# sat-smd.net
KiCad netlist of a schematic drawn in Altium Designer
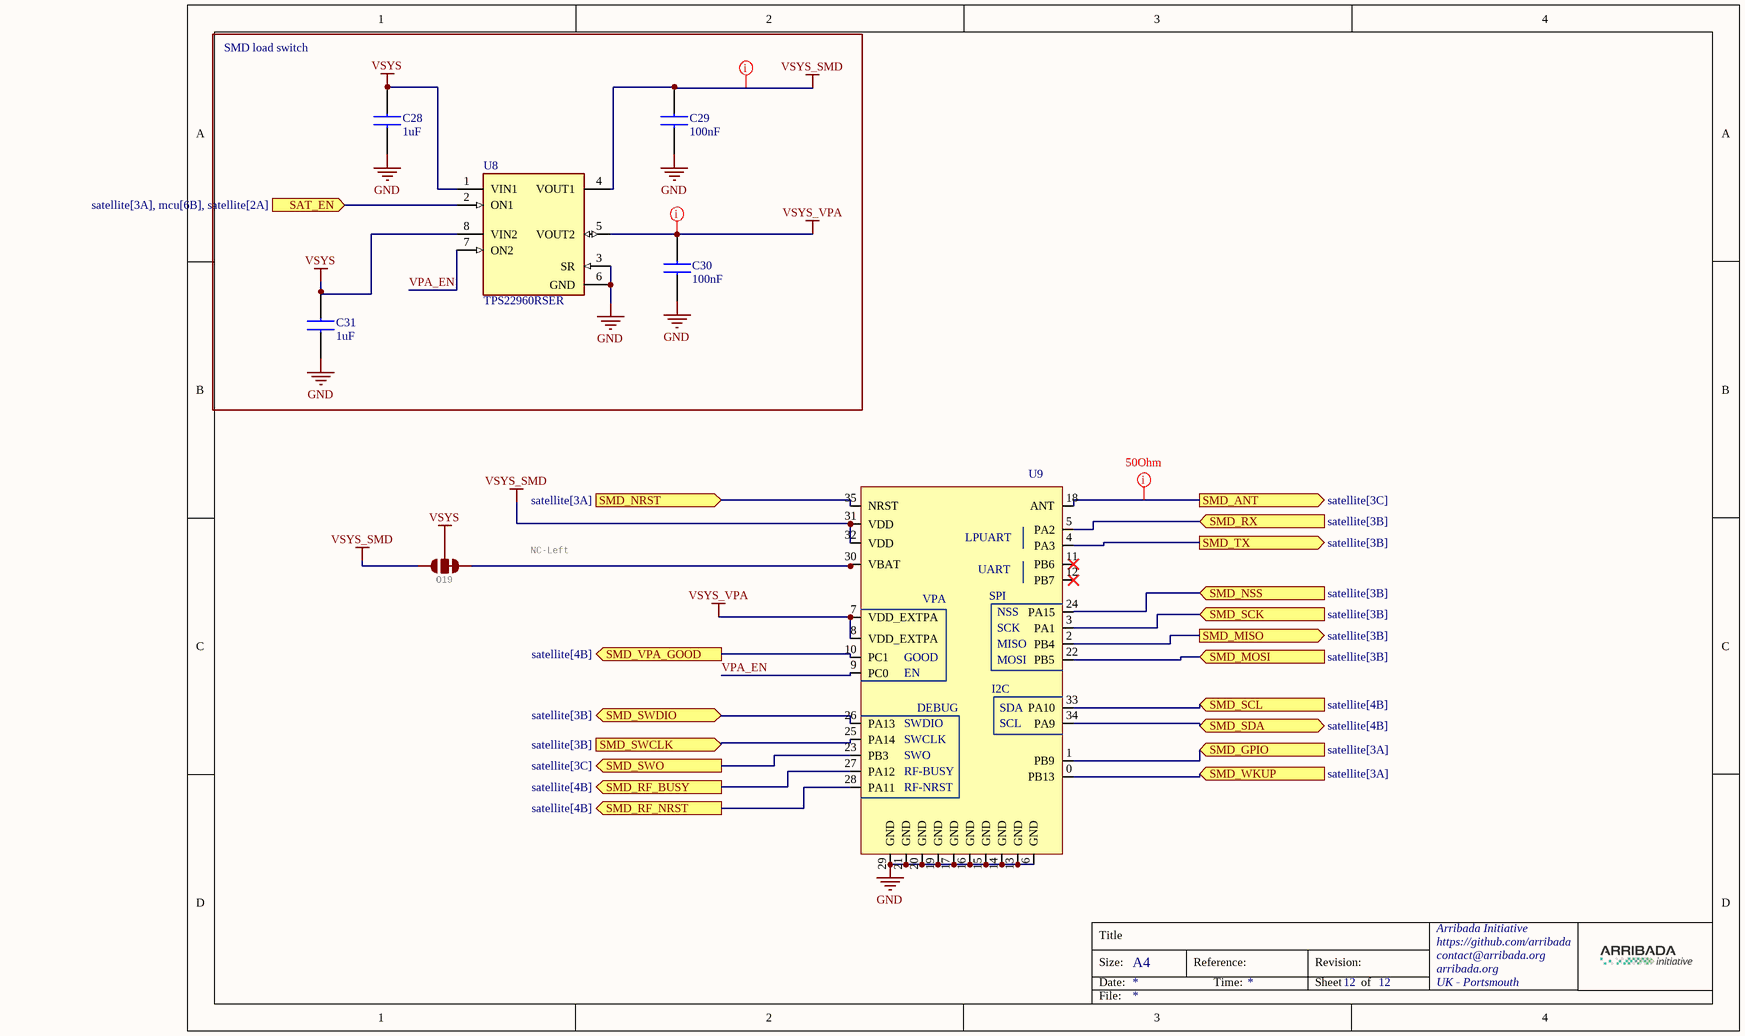
[diagram p0: sat-smd.SchDoc]

(export (version "E")
  (design (tool "Eeschema 10.0.6"))
  (components
    (comp (ref "C28")
      (value "1uF")
      (footprint "CAPC1005X55N")
      (description "Multilayer Ceramic Capacitors MLCC - SMD/SMT 1.0UF 10V 10% 0402")
      (fields
        (field (name "MANUFACTURER_PART_NUMBER") "GRM155Z71A105KE01J")
        (field (name "MOUSER PART NUMBER") "81-GRM155Z71A105KE1J")
      )
      (libsource (lib "stm32wl-dev") (part "GRM155Z71A105KE01J"))
    )
    (comp (ref "C29")
      (value "100nF")
      (footprint "0402")
      (description "Multilayer Ceramic Capacitors MLCC - SMD/SMT 0.1 uF 16 VDC 10% 0402 X7R")
      (fields
        (field (name "MANUFACTURER_PART_NUMBER") "CC0402KRX7R7BB104")
        (field (name "MANUFACTURER") "YAGEO")
      )
      (libsource (lib "stm32wl-dev") (part "GRM155R71C104KA88D"))
    )
    (comp (ref "C30")
      (value "100nF")
      (footprint "0402")
      (description "Multilayer Ceramic Capacitors MLCC - SMD/SMT 0.1 uF 16 VDC 10% 0402 X7R")
      (fields
        (field (name "MANUFACTURER_PART_NUMBER") "CC0402KRX7R7BB104")
        (field (name "MANUFACTURER") "YAGEO")
      )
      (libsource (lib "stm32wl-dev") (part "GRM155R71C104KA88D"))
    )
    (comp (ref "C31")
      (value "1uF")
      (footprint "CAPC1005X55N")
      (description "Multilayer Ceramic Capacitors MLCC - SMD/SMT 1.0UF 10V 10% 0402")
      (fields
        (field (name "MANUFACTURER_PART_NUMBER") "GRM155Z71A105KE01J")
        (field (name "MOUSER PART NUMBER") "81-GRM155Z71A105KE1J")
      )
      (libsource (lib "stm32wl-dev") (part "GRM155Z71A105KE01J"))
    )
    (comp (ref "O19")
      (value "NC-Left")
      (footprint "SMT-JUMPER_3_2-NCLEFT_TRACE_SILK")
      (libsource (lib "stm32wl-dev") (part "JUMPER-SMT_3_2-NCLEFT_TRACE_SILK"))
    )
    (comp (ref "U8")
      (value "TPS22960RSER")
      (footprint "stm32wl-dev:TPS22960RSER")
      (description "Power Switch ICs - Power Distribution Low Input VTG Dual L oad Switch")
      (fields (field (name "MOUSER PART NUMBER") "595-TPS22960RSER"))
      (libsource (lib "stm32wl-dev") (part "TPS22960RSER"))
    )
    (comp (ref "U9")
      (value "stm32wl-SMD")
      (footprint "stm32wl-SMD_noLegs")
      (description "Arribada SMD module Argos comunication with PA GR5504")
      (libsource (lib "stm32wl-dev") (part "stm32wl-SMD"))
    )
  )
  (nets
    (net (code "1") (name "/SAT_EN") (class "Default")
      (node (ref "U8") (pin "2") (pinfunction "ON1_2") (pintype "input"))
    )
    (net (code "2") (name "/SMD_ANT") (class "Default")
      (node (ref "U9") (pin "18") (pinfunction "ANT_18") (pintype "passive"))
    )
    (net (code "3") (name "/SMD_GPIO") (class "Default")
      (node (ref "U9") (pin "1") (pinfunction "PB9_1") (pintype "passive"))
    )
    (net (code "4") (name "/SMD_MISO") (class "Default")
      (node (ref "U9") (pin "2") (pinfunction "PB4_2") (pintype "passive"))
    )
    (net (code "5") (name "/SMD_MOSI") (class "Default")
      (node (ref "U9") (pin "22") (pinfunction "PB5_22") (pintype "passive"))
    )
    (net (code "6") (name "/SMD_NRST") (class "Default")
      (node (ref "U9") (pin "35") (pinfunction "NRST_35") (pintype "input"))
    )
    (net (code "7") (name "/SMD_NSS") (class "Default")
      (node (ref "U9") (pin "24") (pinfunction "PA15_24") (pintype "passive"))
    )
    (net (code "8") (name "/SMD_RF_BUSY") (class "Default")
      (node (ref "U9") (pin "27") (pinfunction "PA12_27") (pintype "passive"))
    )
    (net (code "9") (name "/SMD_RF_NRST") (class "Default")
      (node (ref "U9") (pin "28") (pinfunction "PA11_28") (pintype "passive"))
    )
    (net (code "10") (name "/SMD_RX") (class "Default")
      (node (ref "U9") (pin "5") (pinfunction "PA2_5") (pintype "passive"))
    )
    (net (code "11") (name "/SMD_SCK") (class "Default")
      (node (ref "U9") (pin "3") (pinfunction "PA1_3") (pintype "passive"))
    )
    (net (code "12") (name "/SMD_SCL") (class "Default")
      (node (ref "U9") (pin "33") (pinfunction "PA10_33") (pintype "passive"))
    )
    (net (code "13") (name "/SMD_SDA") (class "Default")
      (node (ref "U9") (pin "34") (pinfunction "PA9_34") (pintype "passive"))
    )
    (net (code "14") (name "/SMD_SWCLK") (class "Default")
      (node (ref "U9") (pin "25") (pinfunction "PA14_25") (pintype "passive"))
    )
    (net (code "15") (name "/SMD_SWDIO") (class "Default")
      (node (ref "U9") (pin "26") (pinfunction "PA13_26") (pintype "passive"))
    )
    (net (code "16") (name "/SMD_SWO") (class "Default")
      (node (ref "U9") (pin "23") (pinfunction "PB3_23") (pintype "passive"))
    )
    (net (code "17") (name "/SMD_TX") (class "Default")
      (node (ref "U9") (pin "4") (pinfunction "PA3_4") (pintype "passive"))
    )
    (net (code "18") (name "/SMD_VPA_GOOD") (class "Default")
      (node (ref "U9") (pin "10") (pinfunction "PC1_10") (pintype "passive"))
    )
    (net (code "19") (name "/SMD_WKUP") (class "Default")
      (node (ref "U9") (pin "0") (pinfunction "PB13_0") (pintype "passive"))
    )
    (net (code "20") (name "/VPA_EN") (class "Default")
      (node (ref "U8") (pin "7") (pinfunction "ON2_7") (pintype "input"))
      (node (ref "U9") (pin "9") (pinfunction "PC0_9") (pintype "output"))
    )
    (net (code "21") (name "GND") (class "Default")
      (node (ref "C28") (pin "1") (pinfunction "1_1") (pintype "passive"))
      (node (ref "C29") (pin "2") (pinfunction "2_2") (pintype "passive"))
      (node (ref "C30") (pin "2") (pinfunction "2_2") (pintype "passive"))
      (node (ref "C31") (pin "1") (pinfunction "1_1") (pintype "passive"))
      (node (ref "U8") (pin "3") (pinfunction "SR_3") (pintype "input"))
      (node (ref "U8") (pin "6") (pinfunction "GND_6") (pintype "passive"))
      (node (ref "U9") (pin "13") (pinfunction "GND_13") (pintype "passive"))
      (node (ref "U9") (pin "14") (pinfunction "GND_14") (pintype "passive"))
      (node (ref "U9") (pin "15") (pinfunction "GND_15") (pintype "passive"))
      (node (ref "U9") (pin "16") (pinfunction "GND_16") (pintype "passive"))
      (node (ref "U9") (pin "17") (pinfunction "GND_17") (pintype "passive"))
      (node (ref "U9") (pin "19") (pinfunction "GND_19") (pintype "passive"))
      (node (ref "U9") (pin "20") (pinfunction "GND_20") (pintype "passive"))
      (node (ref "U9") (pin "21") (pinfunction "GND_21") (pintype "passive"))
      (node (ref "U9") (pin "29") (pinfunction "GND_29") (pintype "passive"))
      (node (ref "U9") (pin "6") (pinfunction "GND_6") (pintype "passive"))
    )
    (net (code "22") (name "Net-(U9-VBAT)") (class "Default")
      (node (ref "O19") (pin "1") (pinfunction "1_1") (pintype "passive"))
      (node (ref "U9") (pin "30") (pinfunction "VBAT_30") (pintype "passive"))
    )
    (net (code "23") (name "VSYS") (class "Default")
      (node (ref "C28") (pin "2") (pinfunction "2_2") (pintype "passive"))
      (node (ref "C31") (pin "2") (pinfunction "2_2") (pintype "passive"))
      (node (ref "O19") (pin "2") (pinfunction "2_2") (pintype "passive"))
      (node (ref "U8") (pin "1") (pinfunction "VIN1_1") (pintype "power_in"))
      (node (ref "U8") (pin "8") (pinfunction "VIN2_8") (pintype "power_in"))
    )
    (net (code "24") (name "VSYS_SMD") (class "Default")
      (node (ref "C29") (pin "1") (pinfunction "1_1") (pintype "passive"))
      (node (ref "O19") (pin "3") (pinfunction "3_3") (pintype "passive"))
      (node (ref "U8") (pin "4") (pinfunction "VOUT1_4") (pintype "power_in"))
      (node (ref "U9") (pin "31") (pinfunction "VDD_31") (pintype "passive"))
      (node (ref "U9") (pin "32") (pinfunction "VDD_32") (pintype "passive"))
    )
    (net (code "25") (name "VSYS_VPA") (class "Default")
      (node (ref "C30") (pin "1") (pinfunction "1_1") (pintype "passive"))
      (node (ref "U8") (pin "5") (pinfunction "VOUT2_5") (pintype "bidirectional"))
      (node (ref "U9") (pin "7") (pinfunction "VDD_EXTPA_7") (pintype "passive"))
      (node (ref "U9") (pin "8") (pinfunction "VDD_EXTPA_8") (pintype "passive"))
    )
    (net (code "26") (name "unconnected-(U9-PB6-Pad11)") (class "Default")
      (node (ref "U9") (pin "11") (pinfunction "PB6_11") (pintype "passive+no_connect"))
    )
    (net (code "27") (name "unconnected-(U9-PB7-Pad12)") (class "Default")
      (node (ref "U9") (pin "12") (pinfunction "PB7_12") (pintype "passive+no_connect"))
    )
  )
)
